# hw3.net
KiCad netlist of a schematic drawn in EAGLE
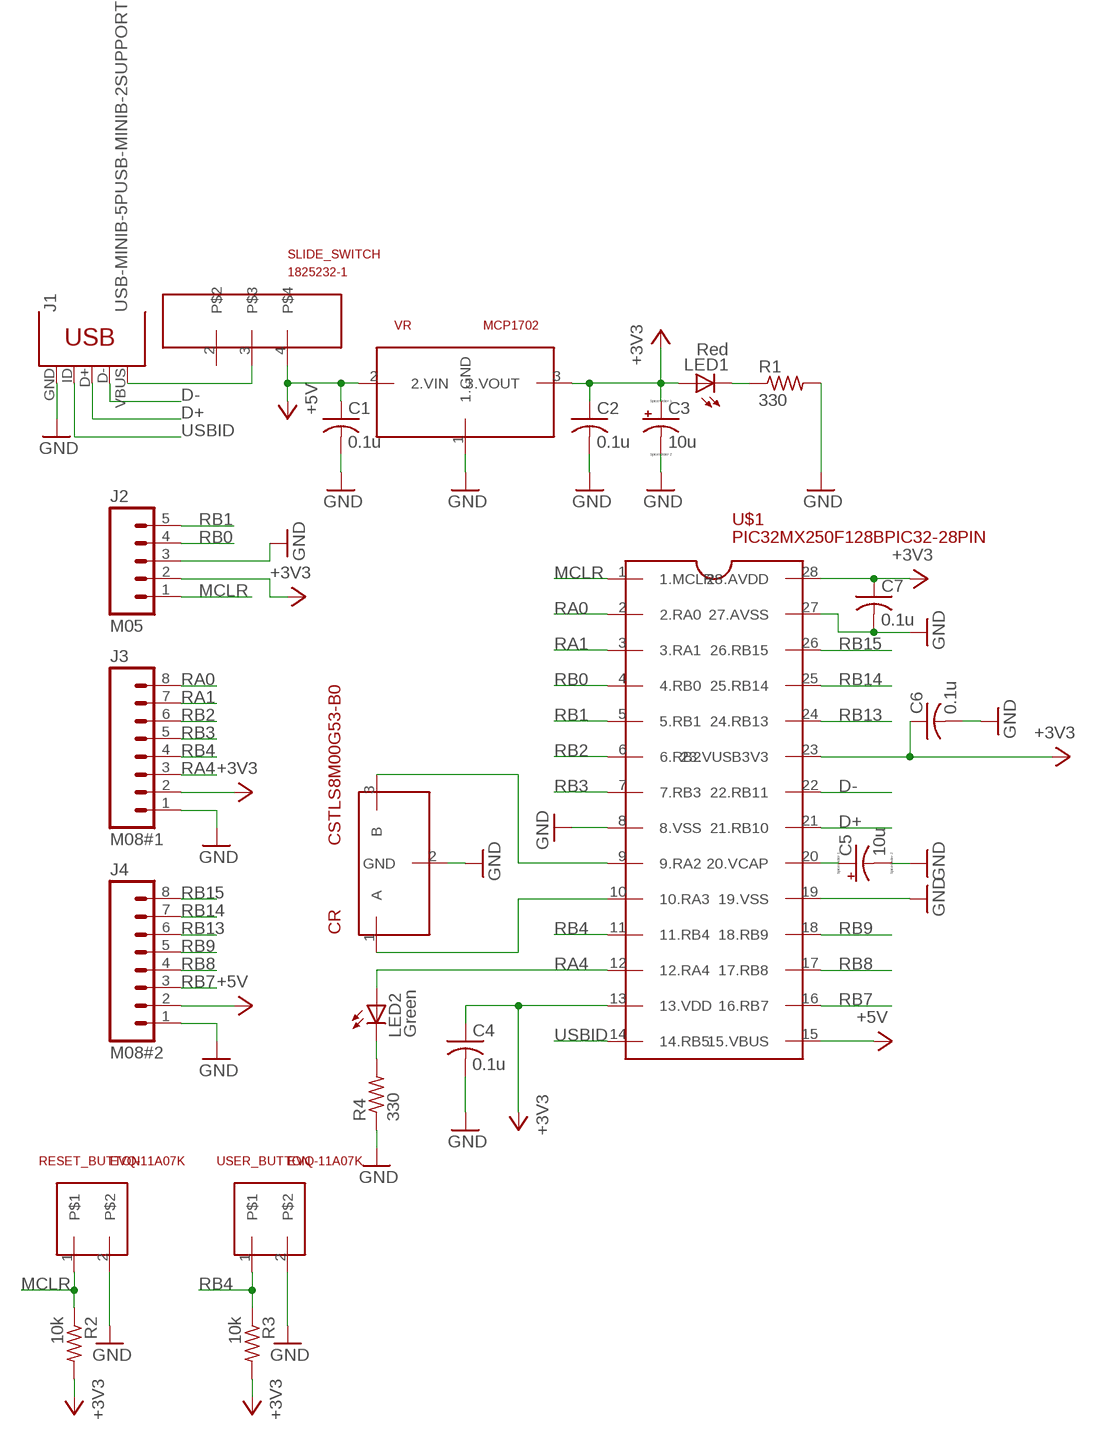
[diagram p0: schematic, sheet 1]

(export (version "E")
  (design (tool "Eeschema 10.0.6"))
  (components
    (comp (ref "C1")
      (value "0.1u")
      (footprint "eagle-import:C025-025X050")
      (libsource (lib "eagle-import") (part "C-US025-025X050"))
    )
    (comp (ref "C2")
      (value "0.1u")
      (footprint "eagle-import:C025-025X050")
      (libsource (lib "eagle-import") (part "C-US025-025X050"))
    )
    (comp (ref "C3")
      (value "10u")
      (footprint "eagle-import:B45181A")
      (libsource (lib "eagle-import") (part "CPOL-USB45181A"))
    )
    (comp (ref "C4")
      (value "0.1u")
      (footprint "eagle-import:C025-025X050")
      (libsource (lib "eagle-import") (part "C-US025-025X050"))
    )
    (comp (ref "C5")
      (value "10u")
      (footprint "eagle-import:B45181A")
      (libsource (lib "eagle-import") (part "CPOL-USB45181A"))
    )
    (comp (ref "C6")
      (value "0.1u")
      (footprint "eagle-import:C025-025X050")
      (libsource (lib "eagle-import") (part "C-US025-025X050"))
    )
    (comp (ref "C7")
      (value "0.1u")
      (footprint "eagle-import:C025-025X050")
      (libsource (lib "eagle-import") (part "C-US025-025X050"))
    )
    (comp (ref "CR")
      (value "CSTLS8M00G53-B0")
      (footprint "eagle-import:1X03_NO_SILK")
      (libsource (lib "eagle-import") (part "CSTLS8M00G53-B0"))
    )
    (comp (ref "J1")
      (value "USB-MINIB-5PUSB-MINIB-2SUPPORT")
      (footprint "eagle-import:USB-MB-H")
      (libsource (lib "eagle-import") (part "USB-MINIB-5PUSB-MINIB-2SUPPORT"))
    )
    (comp (ref "J2")
      (value "M05")
      (footprint "eagle-import:1X05_NO_SILK")
      (libsource (lib "eagle-import") (part "M05NO_SILK"))
    )
    (comp (ref "J3")
      (value "M08#1")
      (footprint "eagle-import:1X08_ROUND")
      (libsource (lib "eagle-import") (part "M08"))
    )
    (comp (ref "J4")
      (value "M08#2")
      (footprint "eagle-import:1X08_ROUND")
      (libsource (lib "eagle-import") (part "M08"))
    )
    (comp (ref "LED1")
      (value "Red")
      (footprint "eagle-import:LED3MM")
      (libsource (lib "eagle-import") (part "LED3MM"))
    )
    (comp (ref "LED2")
      (value "Green")
      (footprint "eagle-import:LED3MM")
      (libsource (lib "eagle-import") (part "LED3MM"))
    )
    (comp (ref "R1")
      (value "330")
      (footprint "eagle-import:0207_10")
      (libsource (lib "eagle-import") (part "R-US_0207/10"))
    )
    (comp (ref "R2")
      (value "10k")
      (footprint "eagle-import:0207_10")
      (libsource (lib "eagle-import") (part "R-US_0207/10"))
    )
    (comp (ref "R3")
      (value "10k")
      (footprint "eagle-import:0207_10")
      (libsource (lib "eagle-import") (part "R-US_0207/10"))
    )
    (comp (ref "R4")
      (value "330")
      (footprint "eagle-import:0207_10")
      (libsource (lib "eagle-import") (part "R-US_0207/10"))
    )
    (comp (ref "RESET_BUTTON")
      (value "EVQ-11A07K")
      (footprint "eagle-import:1X02_NO_SILK_FAR_BOUNDED")
      (libsource (lib "eagle-import") (part "EVQ-11A07K"))
    )
    (comp (ref "SLIDE_SWITCH")
      (value "1825232-1")
      (footprint "eagle-import:1X05_SLIDESWITCH")
      (libsource (lib "eagle-import") (part "1825232-1"))
    )
    (comp (ref "U$1")
      (value "PIC32MX250F128BPIC32-28PIN")
      (footprint "eagle-import:DIL28-3")
      (libsource (lib "eagle-import") (part "PIC32MX250F128BPIC32-28PIN"))
    )
    (comp (ref "USER_BUTTON")
      (value "EVQ-11A07K")
      (footprint "eagle-import:1X02_NO_SILK_FAR_BOUNDED")
      (libsource (lib "eagle-import") (part "EVQ-11A07K"))
    )
    (comp (ref "VR")
      (value "MCP1702")
      (footprint "eagle-import:TO92")
      (libsource (lib "eagle-import") (part "MCP1702"))
    )
  )
  (nets
    (net (code "1") (name "+3V3") (class "Default")
      (node (ref "C2") (pin "1") (pinfunction "1_1") (pintype "passive"))
      (node (ref "C3") (pin "+") (pinfunction "+_+") (pintype "passive"))
      (node (ref "C4") (pin "1") (pinfunction "1_1") (pintype "passive"))
      (node (ref "C6") (pin "1") (pinfunction "1_1") (pintype "passive"))
      (node (ref "C7") (pin "1") (pinfunction "1_1") (pintype "passive"))
      (node (ref "J2") (pin "2") (pinfunction "2_2") (pintype "passive"))
      (node (ref "J3") (pin "2") (pinfunction "2_2") (pintype "passive"))
      (node (ref "LED1") (pin "A") (pinfunction "A_A") (pintype "passive"))
      (node (ref "R2") (pin "2") (pinfunction "2_2") (pintype "passive"))
      (node (ref "R3") (pin "2") (pinfunction "2_2") (pintype "passive"))
      (node (ref "U$1") (pin "13") (pinfunction "13.VDD_13") (pintype "bidirectional"))
      (node (ref "U$1") (pin "23") (pinfunction "23.VUSB3V3_23") (pintype "bidirectional"))
      (node (ref "U$1") (pin "28") (pinfunction "28.AVDD_28") (pintype "bidirectional"))
      (node (ref "VR") (pin "3") (pinfunction "3.VOUT_3") (pintype "bidirectional"))
    )
    (net (code "2") (name "+5V") (class "Default")
      (node (ref "C1") (pin "1") (pinfunction "1_1") (pintype "passive"))
      (node (ref "J4") (pin "2") (pinfunction "2_2") (pintype "passive"))
      (node (ref "SLIDE_SWITCH") (pin "4") (pinfunction "P$4_4") (pintype "bidirectional"))
      (node (ref "U$1") (pin "15") (pinfunction "15.VBUS_15") (pintype "bidirectional"))
      (node (ref "VR") (pin "2") (pinfunction "2.VIN_2") (pintype "bidirectional"))
    )
    (net (code "3") (name "/D+") (class "Default")
      (node (ref "J1") (pin "D+") (pinfunction "D+_D+") (pintype "bidirectional"))
      (node (ref "U$1") (pin "21") (pinfunction "21.RB10_21") (pintype "bidirectional"))
    )
    (net (code "4") (name "/D-") (class "Default")
      (node (ref "J1") (pin "D-") (pinfunction "D-_D-") (pintype "bidirectional"))
      (node (ref "U$1") (pin "22") (pinfunction "22.RB11_22") (pintype "bidirectional"))
    )
    (net (code "5") (name "/MCLR") (class "Default")
      (node (ref "J2") (pin "1") (pinfunction "1_1") (pintype "passive"))
      (node (ref "R2") (pin "1") (pinfunction "1_1") (pintype "passive"))
      (node (ref "RESET_BUTTON") (pin "1") (pinfunction "P$1_1") (pintype "bidirectional"))
      (node (ref "U$1") (pin "1") (pinfunction "1.MCLR_1") (pintype "bidirectional"))
    )
    (net (code "6") (name "/RA0") (class "Default")
      (node (ref "J3") (pin "8") (pinfunction "8_8") (pintype "passive"))
      (node (ref "U$1") (pin "2") (pinfunction "2.RA0_2") (pintype "bidirectional"))
    )
    (net (code "7") (name "/RA1") (class "Default")
      (node (ref "J3") (pin "7") (pinfunction "7_7") (pintype "passive"))
      (node (ref "U$1") (pin "3") (pinfunction "3.RA1_3") (pintype "bidirectional"))
    )
    (net (code "8") (name "/RA4") (class "Default")
      (node (ref "J3") (pin "3") (pinfunction "3_3") (pintype "passive"))
      (node (ref "LED2") (pin "A") (pinfunction "A_A") (pintype "passive"))
      (node (ref "U$1") (pin "12") (pinfunction "12.RA4_12") (pintype "bidirectional"))
    )
    (net (code "9") (name "/RB0") (class "Default")
      (node (ref "J2") (pin "4") (pinfunction "4_4") (pintype "passive"))
      (node (ref "U$1") (pin "4") (pinfunction "4.RB0_4") (pintype "bidirectional"))
    )
    (net (code "10") (name "/RB1") (class "Default")
      (node (ref "J2") (pin "5") (pinfunction "5_5") (pintype "passive"))
      (node (ref "U$1") (pin "5") (pinfunction "5.RB1_5") (pintype "bidirectional"))
    )
    (net (code "11") (name "/RB2") (class "Default")
      (node (ref "J3") (pin "6") (pinfunction "6_6") (pintype "passive"))
      (node (ref "U$1") (pin "6") (pinfunction "6.RB2_6") (pintype "bidirectional"))
    )
    (net (code "12") (name "/RB3") (class "Default")
      (node (ref "J3") (pin "5") (pinfunction "5_5") (pintype "passive"))
      (node (ref "U$1") (pin "7") (pinfunction "7.RB3_7") (pintype "bidirectional"))
    )
    (net (code "13") (name "/RB4") (class "Default")
      (node (ref "J3") (pin "4") (pinfunction "4_4") (pintype "passive"))
      (node (ref "R3") (pin "1") (pinfunction "1_1") (pintype "passive"))
      (node (ref "U$1") (pin "11") (pinfunction "11.RB4_11") (pintype "bidirectional"))
      (node (ref "USER_BUTTON") (pin "1") (pinfunction "P$1_1") (pintype "bidirectional"))
    )
    (net (code "14") (name "/RB7") (class "Default")
      (node (ref "J4") (pin "3") (pinfunction "3_3") (pintype "passive"))
      (node (ref "U$1") (pin "16") (pinfunction "16.RB7_16") (pintype "bidirectional"))
    )
    (net (code "15") (name "/RB8") (class "Default")
      (node (ref "J4") (pin "4") (pinfunction "4_4") (pintype "passive"))
      (node (ref "U$1") (pin "17") (pinfunction "17.RB8_17") (pintype "bidirectional"))
    )
    (net (code "16") (name "/RB9") (class "Default")
      (node (ref "J4") (pin "5") (pinfunction "5_5") (pintype "passive"))
      (node (ref "U$1") (pin "18") (pinfunction "18.RB9_18") (pintype "bidirectional"))
    )
    (net (code "17") (name "/RB13") (class "Default")
      (node (ref "J4") (pin "6") (pinfunction "6_6") (pintype "passive"))
      (node (ref "U$1") (pin "24") (pinfunction "24.RB13_24") (pintype "bidirectional"))
    )
    (net (code "18") (name "/RB14") (class "Default")
      (node (ref "J4") (pin "7") (pinfunction "7_7") (pintype "passive"))
      (node (ref "U$1") (pin "25") (pinfunction "25.RB14_25") (pintype "bidirectional"))
    )
    (net (code "19") (name "/RB15") (class "Default")
      (node (ref "J4") (pin "8") (pinfunction "8_8") (pintype "passive"))
      (node (ref "U$1") (pin "26") (pinfunction "26.RB15_26") (pintype "bidirectional"))
    )
    (net (code "20") (name "/USBID") (class "Default")
      (node (ref "J1") (pin "ID") (pinfunction "ID_ID") (pintype "bidirectional"))
      (node (ref "U$1") (pin "14") (pinfunction "14.RB5_14") (pintype "bidirectional"))
    )
    (net (code "21") (name "GND") (class "Default")
      (node (ref "C1") (pin "2") (pinfunction "2_2") (pintype "passive"))
      (node (ref "C2") (pin "2") (pinfunction "2_2") (pintype "passive"))
      (node (ref "C3") (pin "-") (pinfunction "-_-") (pintype "passive"))
      (node (ref "C4") (pin "2") (pinfunction "2_2") (pintype "passive"))
      (node (ref "C5") (pin "-") (pinfunction "-_-") (pintype "passive"))
      (node (ref "C6") (pin "2") (pinfunction "2_2") (pintype "passive"))
      (node (ref "C7") (pin "2") (pinfunction "2_2") (pintype "passive"))
      (node (ref "CR") (pin "2") (pinfunction "GND_2") (pintype "bidirectional"))
      (node (ref "J1") (pin "GND") (pinfunction "GND_GND") (pintype "bidirectional"))
      (node (ref "J2") (pin "3") (pinfunction "3_3") (pintype "passive"))
      (node (ref "J3") (pin "1") (pinfunction "1_1") (pintype "passive"))
      (node (ref "J4") (pin "1") (pinfunction "1_1") (pintype "passive"))
      (node (ref "R1") (pin "2") (pinfunction "2_2") (pintype "passive"))
      (node (ref "R4") (pin "1") (pinfunction "1_1") (pintype "passive"))
      (node (ref "RESET_BUTTON") (pin "2") (pinfunction "P$2_2") (pintype "bidirectional"))
      (node (ref "U$1") (pin "19") (pinfunction "19.VSS_19") (pintype "bidirectional"))
      (node (ref "U$1") (pin "27") (pinfunction "27.AVSS_27") (pintype "bidirectional"))
      (node (ref "U$1") (pin "8") (pinfunction "8.VSS_8") (pintype "bidirectional"))
      (node (ref "USER_BUTTON") (pin "2") (pinfunction "P$2_2") (pintype "bidirectional"))
      (node (ref "VR") (pin "1") (pinfunction "1.GND_1") (pintype "bidirectional"))
    )
    (net (code "22") (name "Net-(CR-A)") (class "Default")
      (node (ref "CR") (pin "1") (pinfunction "A_1") (pintype "bidirectional"))
      (node (ref "U$1") (pin "10") (pinfunction "10.RA3_10") (pintype "bidirectional"))
    )
    (net (code "23") (name "Net-(CR-B)") (class "Default")
      (node (ref "CR") (pin "3") (pinfunction "B_3") (pintype "bidirectional"))
      (node (ref "U$1") (pin "9") (pinfunction "9.RA2_9") (pintype "bidirectional"))
    )
    (net (code "24") (name "Net-(LED1-C)") (class "Default")
      (node (ref "LED1") (pin "K") (pinfunction "C_K") (pintype "passive"))
      (node (ref "R1") (pin "1") (pinfunction "1_1") (pintype "passive"))
    )
    (net (code "25") (name "Net-(LED2-C)") (class "Default")
      (node (ref "LED2") (pin "K") (pinfunction "C_K") (pintype "passive"))
      (node (ref "R4") (pin "2") (pinfunction "2_2") (pintype "passive"))
    )
    (net (code "26") (name "Net-(SLIDE_SWITCH-P$3)") (class "Default")
      (node (ref "J1") (pin "VBUS") (pinfunction "VBUS_VBUS") (pintype "bidirectional"))
      (node (ref "SLIDE_SWITCH") (pin "3") (pinfunction "P$3_3") (pintype "bidirectional"))
    )
    (net (code "27") (name "Net-(U$1-20.VCAP)") (class "Default")
      (node (ref "C5") (pin "+") (pinfunction "+_+") (pintype "passive"))
      (node (ref "U$1") (pin "20") (pinfunction "20.VCAP_20") (pintype "bidirectional"))
    )
    (net (code "28") (name "unconnected-(SLIDE_SWITCH-P$2-Pad2)") (class "Default")
      (node (ref "SLIDE_SWITCH") (pin "2") (pinfunction "P$2_2") (pintype "bidirectional"))
    )
  )
)
